# led_uv.net
KiCad netlist of a schematic drawn in EAGLE
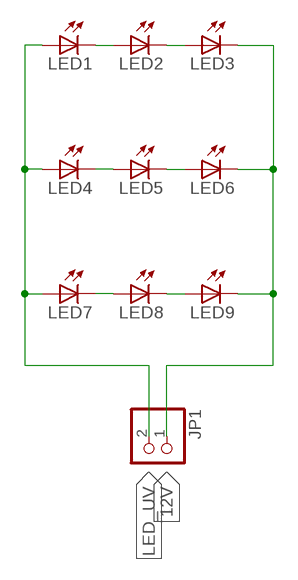
[diagram p0: schematic, sheet 1]

(export (version "E")
  (design (tool "Eeschema 10.0.6"))
  (components
    (comp (ref "JP1")
      (value "PINHD-1X2")
      (footprint "eagle-import:1X02")
      (libsource (lib "eagle-import") (part "PINHD-1X2"))
    )
    (comp (ref "LED1")
      (value "W49180")
      (footprint "eagle-import:Z-POWER-LED-DOME-TYPE")
      (libsource (lib "eagle-import") (part "W49180"))
    )
    (comp (ref "LED2")
      (value "W49180")
      (footprint "eagle-import:Z-POWER-LED-DOME-TYPE")
      (libsource (lib "eagle-import") (part "W49180"))
    )
    (comp (ref "LED3")
      (value "W49180")
      (footprint "eagle-import:Z-POWER-LED-DOME-TYPE")
      (libsource (lib "eagle-import") (part "W49180"))
    )
    (comp (ref "LED4")
      (value "W49180")
      (footprint "eagle-import:Z-POWER-LED-DOME-TYPE")
      (libsource (lib "eagle-import") (part "W49180"))
    )
    (comp (ref "LED5")
      (value "W49180")
      (footprint "eagle-import:Z-POWER-LED-DOME-TYPE")
      (libsource (lib "eagle-import") (part "W49180"))
    )
    (comp (ref "LED6")
      (value "W49180")
      (footprint "eagle-import:Z-POWER-LED-DOME-TYPE")
      (libsource (lib "eagle-import") (part "W49180"))
    )
    (comp (ref "LED7")
      (value "W49180")
      (footprint "eagle-import:Z-POWER-LED-DOME-TYPE")
      (libsource (lib "eagle-import") (part "W49180"))
    )
    (comp (ref "LED8")
      (value "W49180")
      (footprint "eagle-import:Z-POWER-LED-DOME-TYPE")
      (libsource (lib "eagle-import") (part "W49180"))
    )
    (comp (ref "LED9")
      (value "W49180")
      (footprint "eagle-import:Z-POWER-LED-DOME-TYPE")
      (libsource (lib "eagle-import") (part "W49180"))
    )
  )
  (nets
    (net (code "1") (name "12V") (class "Default")
      (node (ref "JP1") (pin "1") (pinfunction "1_1") (pintype "passive"))
      (node (ref "LED3") (pin "C") (pinfunction "C_C") (pintype "passive"))
      (node (ref "LED6") (pin "C") (pinfunction "C_C") (pintype "passive"))
      (node (ref "LED9") (pin "C") (pinfunction "C_C") (pintype "passive"))
    )
    (net (code "2") (name "LED_UV") (class "Default")
      (node (ref "JP1") (pin "2") (pinfunction "2_2") (pintype "passive"))
      (node (ref "LED1") (pin "A") (pinfunction "A_A") (pintype "passive"))
      (node (ref "LED4") (pin "A") (pinfunction "A_A") (pintype "passive"))
      (node (ref "LED7") (pin "A") (pinfunction "A_A") (pintype "passive"))
    )
    (net (code "3") (name "Net-(LED1-PadC)") (class "Default")
      (node (ref "LED1") (pin "C") (pinfunction "C_C") (pintype "passive"))
      (node (ref "LED2") (pin "A") (pinfunction "A_A") (pintype "passive"))
    )
    (net (code "4") (name "Net-(LED2-PadC)") (class "Default")
      (node (ref "LED2") (pin "C") (pinfunction "C_C") (pintype "passive"))
      (node (ref "LED3") (pin "A") (pinfunction "A_A") (pintype "passive"))
    )
    (net (code "5") (name "Net-(LED4-PadC)") (class "Default")
      (node (ref "LED4") (pin "C") (pinfunction "C_C") (pintype "passive"))
      (node (ref "LED5") (pin "A") (pinfunction "A_A") (pintype "passive"))
    )
    (net (code "6") (name "Net-(LED5-PadC)") (class "Default")
      (node (ref "LED5") (pin "C") (pinfunction "C_C") (pintype "passive"))
      (node (ref "LED6") (pin "A") (pinfunction "A_A") (pintype "passive"))
    )
    (net (code "7") (name "Net-(LED7-PadC)") (class "Default")
      (node (ref "LED7") (pin "C") (pinfunction "C_C") (pintype "passive"))
      (node (ref "LED8") (pin "A") (pinfunction "A_A") (pintype "passive"))
    )
    (net (code "8") (name "Net-(LED8-PadC)") (class "Default")
      (node (ref "LED8") (pin "C") (pinfunction "C_C") (pintype "passive"))
      (node (ref "LED9") (pin "A") (pinfunction "A_A") (pintype "passive"))
    )
  )
)
